# untitled.net
KiCad netlist of a schematic drawn in EAGLE
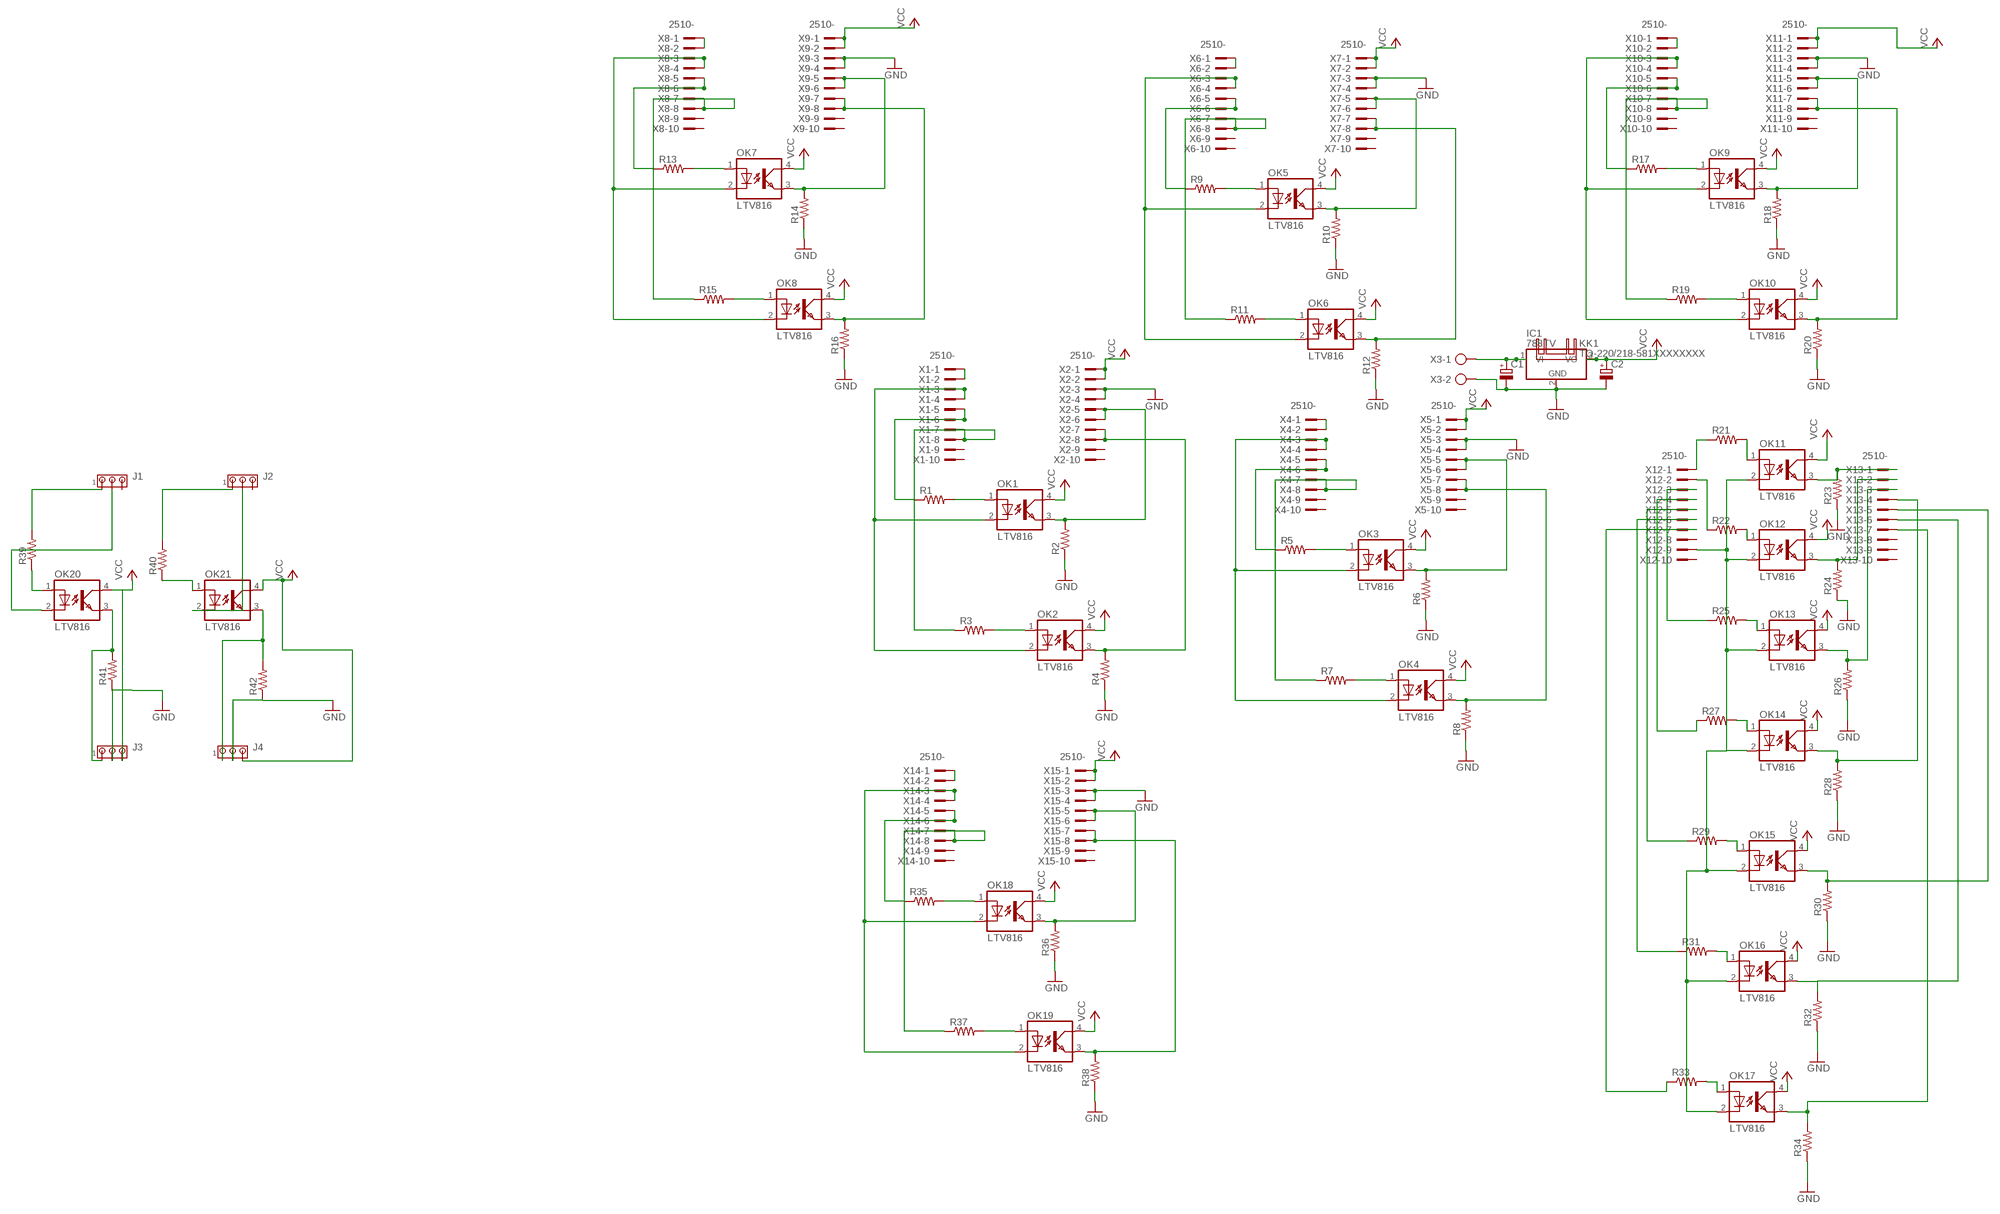
[diagram p0: schematic, sheet 1]

(export (version "E")
  (design (tool "Eeschema 10.0.6"))
  (components
    (comp (ref "C1")
      (value "CPOL-EUE5-13")
      (footprint "eagle-import:E5-13")
      (libsource (lib "eagle-import") (part "CPOL-EUE5-13"))
    )
    (comp (ref "C2")
      (value "CPOL-EUE5-10.5")
      (footprint "eagle-import:E5-10,5")
      (libsource (lib "eagle-import") (part "CPOL-EUE5-10.5"))
    )
    (comp (ref "IC1")
      (value "788TV")
      (footprint "eagle-import:TO220V")
      (libsource (lib "eagle-import") (part "78TV8"))
    )
    (comp (ref "J1")
      (value "MTA03-100")
      (footprint "eagle-import:10X03MTA")
      (libsource (lib "eagle-import") (part "MTA03-100"))
    )
    (comp (ref "J2")
      (value "MTA03-100")
      (footprint "eagle-import:10X03MTA")
      (libsource (lib "eagle-import") (part "MTA03-100"))
    )
    (comp (ref "J3")
      (value "MTA03-100")
      (footprint "eagle-import:10X03MTA")
      (libsource (lib "eagle-import") (part "MTA03-100"))
    )
    (comp (ref "J4")
      (value "MTA03-100")
      (footprint "eagle-import:10X03MTA")
      (libsource (lib "eagle-import") (part "MTA03-100"))
    )
    (comp (ref "KK1")
      (value "TO-220/218-581XXXXXXXX")
      (footprint "eagle-import:581XXXXXXXX")
      (libsource (lib "eagle-import") (part "TO-220/218-581XXXXXXXX"))
    )
    (comp (ref "OK1")
      (value "LTV816")
      (footprint "eagle-import:DIL04")
      (libsource (lib "eagle-import") (part "LTV816"))
    )
    (comp (ref "OK2")
      (value "LTV816")
      (footprint "eagle-import:DIL04")
      (libsource (lib "eagle-import") (part "LTV816"))
    )
    (comp (ref "OK3")
      (value "LTV816")
      (footprint "eagle-import:DIL04")
      (libsource (lib "eagle-import") (part "LTV816"))
    )
    (comp (ref "OK4")
      (value "LTV816")
      (footprint "eagle-import:DIL04")
      (libsource (lib "eagle-import") (part "LTV816"))
    )
    (comp (ref "OK5")
      (value "LTV816")
      (footprint "eagle-import:DIL04")
      (libsource (lib "eagle-import") (part "LTV816"))
    )
    (comp (ref "OK6")
      (value "LTV816")
      (footprint "eagle-import:DIL04")
      (libsource (lib "eagle-import") (part "LTV816"))
    )
    (comp (ref "OK7")
      (value "LTV816")
      (footprint "eagle-import:DIL04")
      (libsource (lib "eagle-import") (part "LTV816"))
    )
    (comp (ref "OK8")
      (value "LTV816")
      (footprint "eagle-import:DIL04")
      (libsource (lib "eagle-import") (part "LTV816"))
    )
    (comp (ref "OK9")
      (value "LTV816")
      (footprint "eagle-import:DIL04")
      (libsource (lib "eagle-import") (part "LTV816"))
    )
    (comp (ref "OK10")
      (value "LTV816")
      (footprint "eagle-import:DIL04")
      (libsource (lib "eagle-import") (part "LTV816"))
    )
    (comp (ref "OK11")
      (value "LTV816")
      (footprint "eagle-import:DIL04")
      (fields (field (name "OC_FARNELL") "unknown") (field (name "OC_NEWARK") "unknown"))
      (libsource (lib "eagle-import") (part "LTV816"))
    )
    (comp (ref "OK12")
      (value "LTV816")
      (footprint "eagle-import:DIL04")
      (fields (field (name "OC_FARNELL") "unknown") (field (name "OC_NEWARK") "unknown"))
      (libsource (lib "eagle-import") (part "LTV816"))
    )
    (comp (ref "OK13")
      (value "LTV816")
      (footprint "eagle-import:DIL04")
      (fields (field (name "OC_FARNELL") "unknown") (field (name "OC_NEWARK") "unknown"))
      (libsource (lib "eagle-import") (part "LTV816"))
    )
    (comp (ref "OK14")
      (value "LTV816")
      (footprint "eagle-import:DIL04")
      (fields (field (name "OC_FARNELL") "unknown") (field (name "OC_NEWARK") "unknown"))
      (libsource (lib "eagle-import") (part "LTV816"))
    )
    (comp (ref "OK15")
      (value "LTV816")
      (footprint "eagle-import:DIL04")
      (fields (field (name "OC_FARNELL") "unknown") (field (name "OC_NEWARK") "unknown"))
      (libsource (lib "eagle-import") (part "LTV816"))
    )
    (comp (ref "OK16")
      (value "LTV816")
      (footprint "eagle-import:DIL04")
      (fields (field (name "OC_FARNELL") "unknown") (field (name "OC_NEWARK") "unknown"))
      (libsource (lib "eagle-import") (part "LTV816"))
    )
    (comp (ref "OK17")
      (value "LTV816")
      (footprint "eagle-import:DIL04")
      (fields (field (name "OC_FARNELL") "unknown") (field (name "OC_NEWARK") "unknown"))
      (libsource (lib "eagle-import") (part "LTV816"))
    )
    (comp (ref "OK18")
      (value "LTV816")
      (footprint "eagle-import:DIL04")
      (libsource (lib "eagle-import") (part "LTV816"))
    )
    (comp (ref "OK19")
      (value "LTV816")
      (footprint "eagle-import:DIL04")
      (libsource (lib "eagle-import") (part "LTV816"))
    )
    (comp (ref "OK20")
      (value "LTV816")
      (footprint "eagle-import:DIL04")
      (fields (field (name "OC_FARNELL") "unknown") (field (name "OC_NEWARK") "unknown"))
      (libsource (lib "eagle-import") (part "LTV816"))
    )
    (comp (ref "OK21")
      (value "LTV816")
      (footprint "eagle-import:DIL04")
      (fields (field (name "OC_FARNELL") "unknown") (field (name "OC_NEWARK") "unknown"))
      (libsource (lib "eagle-import") (part "LTV816"))
    )
    (comp (ref "R1")
      (value "R-US_0207/10")
      (footprint "eagle-import:0207_10")
      (libsource (lib "eagle-import") (part "R-US_0207/10"))
    )
    (comp (ref "R2")
      (value "R-US_0207/10")
      (footprint "eagle-import:0207_10")
      (libsource (lib "eagle-import") (part "R-US_0207/10"))
    )
    (comp (ref "R3")
      (value "R-US_0207/10")
      (footprint "eagle-import:0207_10")
      (libsource (lib "eagle-import") (part "R-US_0207/10"))
    )
    (comp (ref "R4")
      (value "R-US_0207/10")
      (footprint "eagle-import:0207_10")
      (libsource (lib "eagle-import") (part "R-US_0207/10"))
    )
    (comp (ref "R5")
      (value "R-US_0207/10")
      (footprint "eagle-import:0207_10")
      (libsource (lib "eagle-import") (part "R-US_0207/10"))
    )
    (comp (ref "R6")
      (value "R-US_0207/10")
      (footprint "eagle-import:0207_10")
      (libsource (lib "eagle-import") (part "R-US_0207/10"))
    )
    (comp (ref "R7")
      (value "R-US_0207/10")
      (footprint "eagle-import:0207_10")
      (libsource (lib "eagle-import") (part "R-US_0207/10"))
    )
    (comp (ref "R8")
      (value "R-US_0207/10")
      (footprint "eagle-import:0207_10")
      (libsource (lib "eagle-import") (part "R-US_0207/10"))
    )
    (comp (ref "R9")
      (value "R-US_0207/10")
      (footprint "eagle-import:0207_10")
      (libsource (lib "eagle-import") (part "R-US_0207/10"))
    )
    (comp (ref "R10")
      (value "R-US_0207/10")
      (footprint "eagle-import:0207_10")
      (libsource (lib "eagle-import") (part "R-US_0207/10"))
    )
    (comp (ref "R11")
      (value "R-US_0207/10")
      (footprint "eagle-import:0207_10")
      (libsource (lib "eagle-import") (part "R-US_0207/10"))
    )
    (comp (ref "R12")
      (value "R-US_0207/10")
      (footprint "eagle-import:0207_10")
      (libsource (lib "eagle-import") (part "R-US_0207/10"))
    )
    (comp (ref "R13")
      (value "R-US_0207/10")
      (footprint "eagle-import:0207_10")
      (libsource (lib "eagle-import") (part "R-US_0207/10"))
    )
    (comp (ref "R14")
      (value "R-US_0207/10")
      (footprint "eagle-import:0207_10")
      (libsource (lib "eagle-import") (part "R-US_0207/10"))
    )
    (comp (ref "R15")
      (value "R-US_0207/10")
      (footprint "eagle-import:0207_10")
      (libsource (lib "eagle-import") (part "R-US_0207/10"))
    )
    (comp (ref "R16")
      (value "R-US_0207/10")
      (footprint "eagle-import:0207_10")
      (libsource (lib "eagle-import") (part "R-US_0207/10"))
    )
    (comp (ref "R17")
      (value "R-US_0207/10")
      (footprint "eagle-import:0207_10")
      (libsource (lib "eagle-import") (part "R-US_0207/10"))
    )
    (comp (ref "R18")
      (value "R-US_0207/10")
      (footprint "eagle-import:0207_10")
      (libsource (lib "eagle-import") (part "R-US_0207/10"))
    )
    (comp (ref "R19")
      (value "R-US_0207/10")
      (footprint "eagle-import:0207_10")
      (libsource (lib "eagle-import") (part "R-US_0207/10"))
    )
    (comp (ref "R20")
      (value "R-US_0207/10")
      (footprint "eagle-import:0207_10")
      (libsource (lib "eagle-import") (part "R-US_0207/10"))
    )
    (comp (ref "R21")
      (value "R-US_0207/10")
      (footprint "eagle-import:0207_10")
      (libsource (lib "eagle-import") (part "R-US_0207/10"))
    )
    (comp (ref "R22")
      (value "R-US_0207/10")
      (footprint "eagle-import:0207_10")
      (libsource (lib "eagle-import") (part "R-US_0207/10"))
    )
    (comp (ref "R23")
      (value "R-US_0207/10")
      (footprint "eagle-import:0207_10")
      (libsource (lib "eagle-import") (part "R-US_0207/10"))
    )
    (comp (ref "R24")
      (value "R-US_0207/10")
      (footprint "eagle-import:0207_10")
      (libsource (lib "eagle-import") (part "R-US_0207/10"))
    )
    (comp (ref "R25")
      (value "R-US_0207/10")
      (footprint "eagle-import:0207_10")
      (libsource (lib "eagle-import") (part "R-US_0207/10"))
    )
    (comp (ref "R26")
      (value "R-US_0207/10")
      (footprint "eagle-import:0207_10")
      (libsource (lib "eagle-import") (part "R-US_0207/10"))
    )
    (comp (ref "R27")
      (value "R-US_0207/10")
      (footprint "eagle-import:0207_10")
      (libsource (lib "eagle-import") (part "R-US_0207/10"))
    )
    (comp (ref "R28")
      (value "R-US_0207/10")
      (footprint "eagle-import:0207_10")
      (libsource (lib "eagle-import") (part "R-US_0207/10"))
    )
    (comp (ref "R29")
      (value "R-US_0207/10")
      (footprint "eagle-import:0207_10")
      (libsource (lib "eagle-import") (part "R-US_0207/10"))
    )
    (comp (ref "R30")
      (value "R-US_0207/10")
      (footprint "eagle-import:0207_10")
      (libsource (lib "eagle-import") (part "R-US_0207/10"))
    )
    (comp (ref "R31")
      (value "R-US_0207/10")
      (footprint "eagle-import:0207_10")
      (libsource (lib "eagle-import") (part "R-US_0207/10"))
    )
    (comp (ref "R32")
      (value "R-US_0207/10")
      (footprint "eagle-import:0207_10")
      (libsource (lib "eagle-import") (part "R-US_0207/10"))
    )
    (comp (ref "R33")
      (value "R-US_0207/10")
      (footprint "eagle-import:0207_10")
      (libsource (lib "eagle-import") (part "R-US_0207/10"))
    )
    (comp (ref "R34")
      (value "R-US_0207/10")
      (footprint "eagle-import:0207_10")
      (libsource (lib "eagle-import") (part "R-US_0207/10"))
    )
    (comp (ref "R35")
      (value "R-US_0207/10")
      (footprint "eagle-import:0207_10")
      (libsource (lib "eagle-import") (part "R-US_0207/10"))
    )
    (comp (ref "R36")
      (value "R-US_0207/10")
      (footprint "eagle-import:0207_10")
      (libsource (lib "eagle-import") (part "R-US_0207/10"))
    )
    (comp (ref "R37")
      (value "R-US_0207/10")
      (footprint "eagle-import:0207_10")
      (libsource (lib "eagle-import") (part "R-US_0207/10"))
    )
    (comp (ref "R38")
      (value "R-US_0207/10")
      (footprint "eagle-import:0207_10")
      (libsource (lib "eagle-import") (part "R-US_0207/10"))
    )
    (comp (ref "R39")
      (value "R-US_0207/10")
      (footprint "eagle-import:0207_10")
      (libsource (lib "eagle-import") (part "R-US_0207/10"))
    )
    (comp (ref "R40")
      (value "R-US_0207/10")
      (footprint "eagle-import:0207_10")
      (libsource (lib "eagle-import") (part "R-US_0207/10"))
    )
    (comp (ref "R41")
      (value "R-US_0207/10")
      (footprint "eagle-import:0207_10")
      (libsource (lib "eagle-import") (part "R-US_0207/10"))
    )
    (comp (ref "R42")
      (value "R-US_0207/10")
      (footprint "eagle-import:0207_10")
      (libsource (lib "eagle-import") (part "R-US_0207/10"))
    )
    (comp (ref "X1")
      (value "2510-")
      (footprint "eagle-import:PAK100_2500-10")
      (fields (field (name "MF") "3M") (field (name "MPN") "2510-6002UB"))
      (libsource (lib "eagle-import") (part "2510-"))
    )
    (comp (ref "X2")
      (value "2510-")
      (footprint "eagle-import:PAK100_2500-10")
      (fields (field (name "MF") "3M") (field (name "MPN") "2510-6002UB"))
      (libsource (lib "eagle-import") (part "2510-"))
    )
    (comp (ref "X3")
      (value "AK300/2")
      (footprint "eagle-import:AK300_2")
      (libsource (lib "eagle-import") (part "AK300/2"))
    )
    (comp (ref "X4")
      (value "2510-")
      (footprint "eagle-import:PAK100_2500-10")
      (fields (field (name "MF") "3M") (field (name "MPN") "2510-6002UB"))
      (libsource (lib "eagle-import") (part "2510-"))
    )
    (comp (ref "X5")
      (value "2510-")
      (footprint "eagle-import:PAK100_2500-10")
      (fields (field (name "MF") "3M") (field (name "MPN") "2510-6002UB"))
      (libsource (lib "eagle-import") (part "2510-"))
    )
    (comp (ref "X6")
      (value "2510-")
      (footprint "eagle-import:PAK100_2500-10")
      (fields (field (name "MF") "3M") (field (name "MPN") "2510-6002UB"))
      (libsource (lib "eagle-import") (part "2510-"))
    )
    (comp (ref "X7")
      (value "2510-")
      (footprint "eagle-import:PAK100_2500-10")
      (fields (field (name "MF") "3M") (field (name "MPN") "2510-6002UB"))
      (libsource (lib "eagle-import") (part "2510-"))
    )
    (comp (ref "X8")
      (value "2510-")
      (footprint "eagle-import:PAK100_2500-10")
      (fields (field (name "MF") "3M") (field (name "MPN") "2510-6002UB"))
      (libsource (lib "eagle-import") (part "2510-"))
    )
    (comp (ref "X9")
      (value "2510-")
      (footprint "eagle-import:PAK100_2500-10")
      (fields (field (name "MF") "3M") (field (name "MPN") "2510-6002UB"))
      (libsource (lib "eagle-import") (part "2510-"))
    )
    (comp (ref "X10")
      (value "2510-")
      (footprint "eagle-import:PAK100_2500-10")
      (fields (field (name "MF") "3M") (field (name "MPN") "2510-6002UB"))
      (libsource (lib "eagle-import") (part "2510-"))
    )
    (comp (ref "X11")
      (value "2510-")
      (footprint "eagle-import:PAK100_2500-10")
      (fields (field (name "MF") "3M") (field (name "MPN") "2510-6002UB"))
      (libsource (lib "eagle-import") (part "2510-"))
    )
    (comp (ref "X12")
      (value "2510-")
      (footprint "eagle-import:PAK100_2500-10")
      (fields (field (name "MF") "3M") (field (name "MPN") "2510-6002UB"))
      (libsource (lib "eagle-import") (part "2510-"))
    )
    (comp (ref "X13")
      (value "2510-")
      (footprint "eagle-import:PAK100_2500-10")
      (fields (field (name "MF") "3M") (field (name "MPN") "2510-6002UB"))
      (libsource (lib "eagle-import") (part "2510-"))
    )
    (comp (ref "X14")
      (value "2510-")
      (footprint "eagle-import:PAK100_2500-10")
      (fields (field (name "MF") "3M") (field (name "MPN") "2510-6002UB"))
      (libsource (lib "eagle-import") (part "2510-"))
    )
    (comp (ref "X15")
      (value "2510-")
      (footprint "eagle-import:PAK100_2500-10")
      (fields (field (name "MF") "3M") (field (name "MPN") "2510-6002UB"))
      (libsource (lib "eagle-import") (part "2510-"))
    )
  )
  (nets
    (net (code "1") (name "GND") (class "Default")
      (node (ref "C1") (pin "-") (pinfunction "-_-") (pintype "passive"))
      (node (ref "C2") (pin "-") (pinfunction "-_-") (pintype "passive"))
      (node (ref "IC1") (pin "2") (pinfunction "GND_2") (pintype "passive"))
      (node (ref "J3") (pin "2") (pinfunction "2_2") (pintype "passive"))
      (node (ref "J4") (pin "2") (pinfunction "2_2") (pintype "passive"))
      (node (ref "R10") (pin "1") (pinfunction "1_1") (pintype "passive"))
      (node (ref "R12") (pin "1") (pinfunction "1_1") (pintype "passive"))
      (node (ref "R14") (pin "1") (pinfunction "1_1") (pintype "passive"))
      (node (ref "R16") (pin "1") (pinfunction "1_1") (pintype "passive"))
      (node (ref "R18") (pin "1") (pinfunction "1_1") (pintype "passive"))
      (node (ref "R2") (pin "1") (pinfunction "1_1") (pintype "passive"))
      (node (ref "R20") (pin "1") (pinfunction "1_1") (pintype "passive"))
      (node (ref "R23") (pin "1") (pinfunction "1_1") (pintype "passive"))
      (node (ref "R24") (pin "1") (pinfunction "1_1") (pintype "passive"))
      (node (ref "R26") (pin "1") (pinfunction "1_1") (pintype "passive"))
      (node (ref "R28") (pin "1") (pinfunction "1_1") (pintype "passive"))
      (node (ref "R30") (pin "1") (pinfunction "1_1") (pintype "passive"))
      (node (ref "R32") (pin "1") (pinfunction "1_1") (pintype "passive"))
      (node (ref "R34") (pin "1") (pinfunction "1_1") (pintype "passive"))
      (node (ref "R36") (pin "1") (pinfunction "1_1") (pintype "passive"))
      (node (ref "R38") (pin "1") (pinfunction "1_1") (pintype "passive"))
      (node (ref "R4") (pin "1") (pinfunction "1_1") (pintype "passive"))
      (node (ref "R41") (pin "1") (pinfunction "1_1") (pintype "passive"))
      (node (ref "R42") (pin "1") (pinfunction "1_1") (pintype "passive"))
      (node (ref "R6") (pin "1") (pinfunction "1_1") (pintype "passive"))
      (node (ref "R8") (pin "1") (pinfunction "1_1") (pintype "passive"))
      (node (ref "X11") (pin "3") (pinfunction "KL_3") (pintype "passive"))
      (node (ref "X11") (pin "4") (pinfunction "KL_4") (pintype "passive"))
      (node (ref "X15") (pin "3") (pinfunction "KL_3") (pintype "passive"))
      (node (ref "X15") (pin "4") (pinfunction "KL_4") (pintype "passive"))
      (node (ref "X2") (pin "3") (pinfunction "KL_3") (pintype "passive"))
      (node (ref "X2") (pin "4") (pinfunction "KL_4") (pintype "passive"))
      (node (ref "X3") (pin "2") (pinfunction "KL_2") (pintype "passive"))
      (node (ref "X5") (pin "3") (pinfunction "KL_3") (pintype "passive"))
      (node (ref "X5") (pin "4") (pinfunction "KL_4") (pintype "passive"))
      (node (ref "X7") (pin "3") (pinfunction "KL_3") (pintype "passive"))
      (node (ref "X7") (pin "4") (pinfunction "KL_4") (pintype "passive"))
      (node (ref "X9") (pin "3") (pinfunction "KL_3") (pintype "passive"))
      (node (ref "X9") (pin "4") (pinfunction "KL_4") (pintype "passive"))
    )
    (net (code "2") (name "Net-(IC1-VI)") (class "Default")
      (node (ref "C1") (pin "+") (pinfunction "+_+") (pintype "passive"))
      (node (ref "IC1") (pin "1") (pinfunction "VI_1") (pintype "input"))
      (node (ref "X3") (pin "1") (pinfunction "KL_1") (pintype "passive"))
    )
    (net (code "3") (name "Net-(J1-Pad1)") (class "Default")
      (node (ref "J1") (pin "1") (pinfunction "1_1") (pintype "passive"))
      (node (ref "R39") (pin "2") (pinfunction "2_2") (pintype "passive"))
    )
    (net (code "4") (name "Net-(J2-Pad1)") (class "Default")
      (node (ref "J2") (pin "1") (pinfunction "1_1") (pintype "passive"))
      (node (ref "R40") (pin "2") (pinfunction "2_2") (pintype "passive"))
    )
    (net (code "5") (name "Net-(OK1-A)") (class "Default")
      (node (ref "OK1") (pin "1") (pinfunction "A_1") (pintype "passive"))
      (node (ref "R1") (pin "2") (pinfunction "2_2") (pintype "passive"))
    )
    (net (code "6") (name "Net-(OK1-C)") (class "Default")
      (node (ref "OK1") (pin "2") (pinfunction "C_2") (pintype "passive"))
      (node (ref "OK2") (pin "2") (pinfunction "C_2") (pintype "passive"))
      (node (ref "X1") (pin "3") (pinfunction "KL_3") (pintype "passive"))
      (node (ref "X1") (pin "4") (pinfunction "KL_4") (pintype "passive"))
    )
    (net (code "7") (name "Net-(OK1-EMIT)") (class "Default")
      (node (ref "OK1") (pin "3") (pinfunction "EMIT_3") (pintype "passive"))
      (node (ref "R2") (pin "2") (pinfunction "2_2") (pintype "passive"))
      (node (ref "X2") (pin "5") (pinfunction "KL_5") (pintype "passive"))
      (node (ref "X2") (pin "6") (pinfunction "KL_6") (pintype "passive"))
    )
    (net (code "8") (name "Net-(OK2-A)") (class "Default")
      (node (ref "OK2") (pin "1") (pinfunction "A_1") (pintype "passive"))
      (node (ref "R3") (pin "2") (pinfunction "2_2") (pintype "passive"))
    )
    (net (code "9") (name "Net-(OK2-EMIT)") (class "Default")
      (node (ref "OK2") (pin "3") (pinfunction "EMIT_3") (pintype "passive"))
      (node (ref "R4") (pin "2") (pinfunction "2_2") (pintype "passive"))
      (node (ref "X2") (pin "7") (pinfunction "KL_7") (pintype "passive"))
      (node (ref "X2") (pin "8") (pinfunction "KL_8") (pintype "passive"))
    )
    (net (code "10") (name "Net-(OK3-A)") (class "Default")
      (node (ref "OK3") (pin "1") (pinfunction "A_1") (pintype "passive"))
      (node (ref "R5") (pin "2") (pinfunction "2_2") (pintype "passive"))
    )
    (net (code "11") (name "Net-(OK3-C)") (class "Default")
      (node (ref "OK3") (pin "2") (pinfunction "C_2") (pintype "passive"))
      (node (ref "OK4") (pin "2") (pinfunction "C_2") (pintype "passive"))
      (node (ref "X4") (pin "3") (pinfunction "KL_3") (pintype "passive"))
      (node (ref "X4") (pin "4") (pinfunction "KL_4") (pintype "passive"))
    )
    (net (code "12") (name "Net-(OK3-EMIT)") (class "Default")
      (node (ref "OK3") (pin "3") (pinfunction "EMIT_3") (pintype "passive"))
      (node (ref "R6") (pin "2") (pinfunction "2_2") (pintype "passive"))
      (node (ref "X5") (pin "5") (pinfunction "KL_5") (pintype "passive"))
      (node (ref "X5") (pin "6") (pinfunction "KL_6") (pintype "passive"))
    )
    (net (code "13") (name "Net-(OK4-A)") (class "Default")
      (node (ref "OK4") (pin "1") (pinfunction "A_1") (pintype "passive"))
      (node (ref "R7") (pin "2") (pinfunction "2_2") (pintype "passive"))
    )
    (net (code "14") (name "Net-(OK4-EMIT)") (class "Default")
      (node (ref "OK4") (pin "3") (pinfunction "EMIT_3") (pintype "passive"))
      (node (ref "R8") (pin "2") (pinfunction "2_2") (pintype "passive"))
      (node (ref "X5") (pin "7") (pinfunction "KL_7") (pintype "passive"))
      (node (ref "X5") (pin "8") (pinfunction "KL_8") (pintype "passive"))
    )
    (net (code "15") (name "Net-(OK5-A)") (class "Default")
      (node (ref "OK5") (pin "1") (pinfunction "A_1") (pintype "passive"))
      (node (ref "R9") (pin "2") (pinfunction "2_2") (pintype "passive"))
    )
    (net (code "16") (name "Net-(OK5-C)") (class "Default")
      (node (ref "OK5") (pin "2") (pinfunction "C_2") (pintype "passive"))
      (node (ref "OK6") (pin "2") (pinfunction "C_2") (pintype "passive"))
      (node (ref "X6") (pin "3") (pinfunction "KL_3") (pintype "passive"))
      (node (ref "X6") (pin "4") (pinfunction "KL_4") (pintype "passive"))
    )
    (net (code "17") (name "Net-(OK5-EMIT)") (class "Default")
      (node (ref "OK5") (pin "3") (pinfunction "EMIT_3") (pintype "passive"))
      (node (ref "R10") (pin "2") (pinfunction "2_2") (pintype "passive"))
      (node (ref "X7") (pin "5") (pinfunction "KL_5") (pintype "passive"))
      (node (ref "X7") (pin "6") (pinfunction "KL_6") (pintype "passive"))
    )
    (net (code "18") (name "Net-(OK6-A)") (class "Default")
      (node (ref "OK6") (pin "1") (pinfunction "A_1") (pintype "passive"))
      (node (ref "R11") (pin "2") (pinfunction "2_2") (pintype "passive"))
    )
    (net (code "19") (name "Net-(OK6-EMIT)") (class "Default")
      (node (ref "OK6") (pin "3") (pinfunction "EMIT_3") (pintype "passive"))
      (node (ref "R12") (pin "2") (pinfunction "2_2") (pintype "passive"))
      (node (ref "X7") (pin "7") (pinfunction "KL_7") (pintype "passive"))
      (node (ref "X7") (pin "8") (pinfunction "KL_8") (pintype "passive"))
    )
    (net (code "20") (name "Net-(OK7-A)") (class "Default")
      (node (ref "OK7") (pin "1") (pinfunction "A_1") (pintype "passive"))
      (node (ref "R13") (pin "2") (pinfunction "2_2") (pintype "passive"))
    )
    (net (code "21") (name "Net-(OK7-C)") (class "Default")
      (node (ref "OK7") (pin "2") (pinfunction "C_2") (pintype "passive"))
      (node (ref "OK8") (pin "2") (pinfunction "C_2") (pintype "passive"))
      (node (ref "X8") (pin "3") (pinfunction "KL_3") (pintype "passive"))
      (node (ref "X8") (pin "4") (pinfunction "KL_4") (pintype "passive"))
    )
    (net (code "22") (name "Net-(OK7-EMIT)") (class "Default")
      (node (ref "OK7") (pin "3") (pinfunction "EMIT_3") (pintype "passive"))
      (node (ref "R14") (pin "2") (pinfunction "2_2") (pintype "passive"))
      (node (ref "X9") (pin "5") (pinfunction "KL_5") (pintype "passive"))
      (node (ref "X9") (pin "6") (pinfunction "KL_6") (pintype "passive"))
    )
    (net (code "23") (name "Net-(OK8-A)") (class "Default")
      (node (ref "OK8") (pin "1") (pinfunction "A_1") (pintype "passive"))
      (node (ref "R15") (pin "2") (pinfunction "2_2") (pintype "passive"))
    )
    (net (code "24") (name "Net-(OK8-EMIT)") (class "Default")
      (node (ref "OK8") (pin "3") (pinfunction "EMIT_3") (pintype "passive"))
      (node (ref "R16") (pin "2") (pinfunction "2_2") (pintype "passive"))
      (node (ref "X9") (pin "7") (pinfunction "KL_7") (pintype "passive"))
      (node (ref "X9") (pin "8") (pinfunction "KL_8") (pintype "passive"))
    )
    (net (code "25") (name "Net-(OK9-A)") (class "Default")
      (node (ref "OK9") (pin "1") (pinfunction "A_1") (pintype "passive"))
      (node (ref "R17") (pin "2") (pinfunction "2_2") (pintype "passive"))
    )
    (net (code "26") (name "Net-(OK9-EMIT)") (class "Default")
      (node (ref "OK9") (pin "3") (pinfunction "EMIT_3") (pintype "passive"))
      (node (ref "R18") (pin "2") (pinfunction "2_2") (pintype "passive"))
      (node (ref "X11") (pin "5") (pinfunction "KL_5") (pintype "passive"))
      (node (ref "X11") (pin "6") (pinfunction "KL_6") (pintype "passive"))
    )
    (net (code "27") (name "Net-(OK10-A)") (class "Default")
      (node (ref "OK10") (pin "1") (pinfunction "A_1") (pintype "passive"))
      (node (ref "R19") (pin "2") (pinfunction "2_2") (pintype "passive"))
    )
    (net (code "28") (name "Net-(OK10-C)") (class "Default")
      (node (ref "OK10") (pin "2") (pinfunction "C_2") (pintype "passive"))
      (node (ref "OK9") (pin "2") (pinfunction "C_2") (pintype "passive"))
      (node (ref "X10") (pin "3") (pinfunction "KL_3") (pintype "passive"))
      (node (ref "X10") (pin "4") (pinfunction "KL_4") (pintype "passive"))
    )
    (net (code "29") (name "Net-(OK10-EMIT)") (class "Default")
      (node (ref "OK10") (pin "3") (pinfunction "EMIT_3") (pintype "passive"))
      (node (ref "R20") (pin "2") (pinfunction "2_2") (pintype "passive"))
      (node (ref "X11") (pin "7") (pinfunction "KL_7") (pintype "passive"))
      (node (ref "X11") (pin "8") (pinfunction "KL_8") (pintype "passive"))
    )
    (net (code "30") (name "Net-(OK11-A)") (class "Default")
      (node (ref "OK11") (pin "1") (pinfunction "A_1") (pintype "passive"))
      (node (ref "R21") (pin "2") (pinfunction "2_2") (pintype "passive"))
    )
    (net (code "31") (name "Net-(OK11-C)") (class "Default")
      (node (ref "OK11") (pin "2") (pinfunction "C_2") (pintype "passive"))
      (node (ref "OK12") (pin "2") (pinfunction "C_2") (pintype "passive"))
      (node (ref "OK13") (pin "2") (pinfunction "C_2") (pintype "passive"))
      (node (ref "OK14") (pin "2") (pinfunction "C_2") (pintype "passive"))
      (node (ref "OK15") (pin "2") (pinfunction "C_2") (pintype "passive"))
      (node (ref "OK16") (pin "2") (pinfunction "C_2") (pintype "passive"))
      (node (ref "OK17") (pin "2") (pinfunction "C_2") (pintype "passive"))
      (node (ref "X12") (pin "9") (pinfunction "KL_9") (pintype "passive"))
    )
    (net (code "32") (name "Net-(OK11-EMIT)") (class "Default")
      (node (ref "OK11") (pin "3") (pinfunction "EMIT_3") (pintype "passive"))
      (node (ref "R23") (pin "2") (pinfunction "2_2") (pintype "passive"))
      (node (ref "X13") (pin "1") (pinfunction "KL_1") (pintype "passive"))
    )
    (net (code "33") (name "Net-(OK12-A)") (class "Default")
      (node (ref "OK12") (pin "1") (pinfunction "A_1") (pintype "passive"))
      (node (ref "R22") (pin "2") (pinfunction "2_2") (pintype "passive"))
    )
    (net (code "34") (name "Net-(OK12-EMIT)") (class "Default")
      (node (ref "OK12") (pin "3") (pinfunction "EMIT_3") (pintype "passive"))
      (node (ref "R24") (pin "2") (pinfunction "2_2") (pintype "passive"))
      (node (ref "X13") (pin "2") (pinfunction "KL_2") (pintype "passive"))
    )
    (net (code "35") (name "Net-(OK13-A)") (class "Default")
      (node (ref "OK13") (pin "1") (pinfunction "A_1") (pintype "passive"))
      (node (ref "R25") (pin "2") (pinfunction "2_2") (pintype "passive"))
    )
    (net (code "36") (name "Net-(OK13-EMIT)") (class "Default")
      (node (ref "OK13") (pin "3") (pinfunction "EMIT_3") (pintype "passive"))
      (node (ref "R26") (pin "2") (pinfunction "2_2") (pintype "passive"))
      (node (ref "X13") (pin "3") (pinfunction "KL_3") (pintype "passive"))
    )
    (net (code "37") (name "Net-(OK14-A)") (class "Default")
      (node (ref "OK14") (pin "1") (pinfunction "A_1") (pintype "passive"))
      (node (ref "R27") (pin "2") (pinfunction "2_2") (pintype "passive"))
    )
    (net (code "38") (name "Net-(OK14-EMIT)") (class "Default")
      (node (ref "OK14") (pin "3") (pinfunction "EMIT_3") (pintype "passive"))
      (node (ref "R28") (pin "2") (pinfunction "2_2") (pintype "passive"))
      (node (ref "X13") (pin "4") (pinfunction "KL_4") (pintype "passive"))
    )
    (net (code "39") (name "Net-(OK15-A)") (class "Default")
      (node (ref "OK15") (pin "1") (pinfunction "A_1") (pintype "passive"))
      (node (ref "R29") (pin "2") (pinfunction "2_2") (pintype "passive"))
    )
    (net (code "40") (name "Net-(OK15-EMIT)") (class "Default")
      (node (ref "OK15") (pin "3") (pinfunction "EMIT_3") (pintype "passive"))
      (node (ref "R30") (pin "2") (pinfunction "2_2") (pintype "passive"))
      (node (ref "X13") (pin "5") (pinfunction "KL_5") (pintype "passive"))
    )
    (net (code "41") (name "Net-(OK16-A)") (class "Default")
      (node (ref "OK16") (pin "1") (pinfunction "A_1") (pintype "passive"))
      (node (ref "R31") (pin "2") (pinfunction "2_2") (pintype "passive"))
    )
    (net (code "42") (name "Net-(OK16-EMIT)") (class "Default")
      (node (ref "OK16") (pin "3") (pinfunction "EMIT_3") (pintype "passive"))
      (node (ref "R32") (pin "2") (pinfunction "2_2") (pintype "passive"))
      (node (ref "X13") (pin "6") (pinfunction "KL_6") (pintype "passive"))
    )
    (net (code "43") (name "Net-(OK17-A)") (class "Default")
      (node (ref "OK17") (pin "1") (pinfunction "A_1") (pintype "passive"))
      (node (ref "R33") (pin "2") (pinfunction "2_2") (pintype "passive"))
    )
    (net (code "44") (name "Net-(OK17-EMIT)") (class "Default")
      (node (ref "OK17") (pin "3") (pinfunction "EMIT_3") (pintype "passive"))
      (node (ref "R34") (pin "2") (pinfunction "2_2") (pintype "passive"))
      (node (ref "X13") (pin "7") (pinfunction "KL_7") (pintype "passive"))
    )
    (net (code "45") (name "Net-(OK18-A)") (class "Default")
      (node (ref "OK18") (pin "1") (pinfunction "A_1") (pintype "passive"))
      (node (ref "R35") (pin "2") (pinfunction "2_2") (pintype "passive"))
    )
    (net (code "46") (name "Net-(OK18-C)") (class "Default")
      (node (ref "OK18") (pin "2") (pinfunction "C_2") (pintype "passive"))
      (node (ref "OK19") (pin "2") (pinfunction "C_2") (pintype "passive"))
      (node (ref "X14") (pin "3") (pinfunction "KL_3") (pintype "passive"))
      (node (ref "X14") (pin "4") (pinfunction "KL_4") (pintype "passive"))
    )
    (net (code "47") (name "Net-(OK18-EMIT)") (class "Default")
      (node (ref "OK18") (pin "3") (pinfunction "EMIT_3") (pintype "passive"))
      (node (ref "R36") (pin "2") (pinfunction "2_2") (pintype "passive"))
      (node (ref "X15") (pin "5") (pinfunction "KL_5") (pintype "passive"))
      (node (ref "X15") (pin "6") (pinfunction "KL_6") (pintype "passive"))
    )
    (net (code "48") (name "Net-(OK19-A)") (class "Default")
      (node (ref "OK19") (pin "1") (pinfunction "A_1") (pintype "passive"))
      (node (ref "R37") (pin "2") (pinfunction "2_2") (pintype "passive"))
    )
    (net (code "49") (name "Net-(OK19-EMIT)") (class "Default")
      (node (ref "OK19") (pin "3") (pinfunction "EMIT_3") (pintype "passive"))
      (node (ref "R38") (pin "2") (pinfunction "2_2") (pintype "passive"))
      (node (ref "X15") (pin "7") (pinfunction "KL_7") (pintype "passive"))
      (node (ref "X15") (pin "8") (pinfunction "KL_8") (pintype "passive"))
    )
    (net (code "50") (name "Net-(OK20-A)") (class "Default")
      (node (ref "OK20") (pin "1") (pinfunction "A_1") (pintype "passive"))
      (node (ref "R39") (pin "1") (pinfunction "1_1") (pintype "passive"))
    )
    (net (code "51") (name "Net-(OK20-C)") (class "Default")
      (node (ref "J1") (pin "2") (pinfunction "2_2") (pintype "passive"))
      (node (ref "OK20") (pin "2") (pinfunction "C_2") (pintype "passive"))
    )
    (net (code "52") (name "Net-(OK20-EMIT)") (class "Default")
      (node (ref "J3") (pin "1") (pinfunction "1_1") (pintype "passive"))
      (node (ref "OK20") (pin "3") (pinfunction "EMIT_3") (pintype "passive"))
      (node (ref "R41") (pin "2") (pinfunction "2_2") (pintype "passive"))
    )
    (net (code "53") (name "Net-(OK21-A)") (class "Default")
      (node (ref "OK21") (pin "1") (pinfunction "A_1") (pintype "passive"))
      (node (ref "R40") (pin "1") (pinfunction "1_1") (pintype "passive"))
    )
    (net (code "54") (name "Net-(OK21-C)") (class "Default")
      (node (ref "J2") (pin "2") (pinfunction "2_2") (pintype "passive"))
      (node (ref "OK21") (pin "2") (pinfunction "C_2") (pintype "passive"))
    )
    (net (code "55") (name "Net-(OK21-EMIT)") (class "Default")
      (node (ref "J4") (pin "1") (pinfunction "1_1") (pintype "passive"))
      (node (ref "OK21") (pin "3") (pinfunction "EMIT_3") (pintype "passive"))
      (node (ref "R42") (pin "2") (pinfunction "2_2") (pintype "passive"))
    )
    (net (code "56") (name "Net-(X1A-KL)") (class "Default")
      (node (ref "X1") (pin "1") (pinfunction "KL_1") (pintype "passive"))
      (node (ref "X1") (pin "2") (pinfunction "KL_2") (pintype "passive"))
    )
    (net (code "57") (name "Net-(X1F-KL)") (class "Default")
      (node (ref "R1") (pin "1") (pinfunction "1_1") (pintype "passive"))
      (node (ref "X1") (pin "5") (pinfunction "KL_5") (pintype "passive"))
      (node (ref "X1") (pin "6") (pinfunction "KL_6") (pintype "passive"))
    )
    (net (code "58") (name "Net-(X1H-KL)") (class "Default")
      (node (ref "R3") (pin "1") (pinfunction "1_1") (pintype "passive"))
      (node (ref "X1") (pin "7") (pinfunction "KL_7") (pintype "passive"))
      (node (ref "X1") (pin "8") (pinfunction "KL_8") (pintype "passive"))
    )
    (net (code "59") (name "Net-(X4A-KL)") (class "Default")
      (node (ref "X4") (pin "1") (pinfunction "KL_1") (pintype "passive"))
      (node (ref "X4") (pin "2") (pinfunction "KL_2") (pintype "passive"))
    )
    (net (code "60") (name "Net-(X4F-KL)") (class "Default")
      (node (ref "R5") (pin "1") (pinfunction "1_1") (pintype "passive"))
      (node (ref "X4") (pin "5") (pinfunction "KL_5") (pintype "passive"))
      (node (ref "X4") (pin "6") (pinfunction "KL_6") (pintype "passive"))
    )
    (net (code "61") (name "Net-(X4H-KL)") (class "Default")
      (node (ref "R7") (pin "1") (pinfunction "1_1") (pintype "passive"))
      (node (ref "X4") (pin "7") (pinfunction "KL_7") (pintype "passive"))
      (node (ref "X4") (pin "8") (pinfunction "KL_8") (pintype "passive"))
    )
    (net (code "62") (name "Net-(X6A-KL)") (class "Default")
      (node (ref "X6") (pin "1") (pinfunction "KL_1") (pintype "passive"))
      (node (ref "X6") (pin "2") (pinfunction "KL_2") (pintype "passive"))
    )
    (net (code "63") (name "Net-(X6F-KL)") (class "Default")
      (node (ref "R9") (pin "1") (pinfunction "1_1") (pintype "passive"))
      (node (ref "X6") (pin "5") (pinfunction "KL_5") (pintype "passive"))
      (node (ref "X6") (pin "6") (pinfunction "KL_6") (pintype "passive"))
    )
    (net (code "64") (name "Net-(X6H-KL)") (class "Default")
      (node (ref "R11") (pin "1") (pinfunction "1_1") (pintype "passive"))
      (node (ref "X6") (pin "7") (pinfunction "KL_7") (pintype "passive"))
      (node (ref "X6") (pin "8") (pinfunction "KL_8") (pintype "passive"))
    )
    (net (code "65") (name "Net-(X8A-KL)") (class "Default")
      (node (ref "X8") (pin "1") (pinfunction "KL_1") (pintype "passive"))
      (node (ref "X8") (pin "2") (pinfunction "KL_2") (pintype "passive"))
    )
    (net (code "66") (name "Net-(X8F-KL)") (class "Default")
      (node (ref "R13") (pin "1") (pinfunction "1_1") (pintype "passive"))
      (node (ref "X8") (pin "5") (pinfunction "KL_5") (pintype "passive"))
      (node (ref "X8") (pin "6") (pinfunction "KL_6") (pintype "passive"))
    )
    (net (code "67") (name "Net-(X8H-KL)") (class "Default")
      (node (ref "R15") (pin "1") (pinfunction "1_1") (pintype "passive"))
      (node (ref "X8") (pin "7") (pinfunction "KL_7") (pintype "passive"))
      (node (ref "X8") (pin "8") (pinfunction "KL_8") (pintype "passive"))
    )
    (net (code "68") (name "Net-(X10A-KL)") (class "Default")
      (node (ref "X10") (pin "1") (pinfunction "KL_1") (pintype "passive"))
      (node (ref "X10") (pin "2") (pinfunction "KL_2") (pintype "passive"))
    )
    (net (code "69") (name "Net-(X10F-KL)") (class "Default")
      (node (ref "R17") (pin "1") (pinfunction "1_1") (pintype "passive"))
      (node (ref "X10") (pin "5") (pinfunction "KL_5") (pintype "passive"))
      (node (ref "X10") (pin "6") (pinfunction "KL_6") (pintype "passive"))
    )
    (net (code "70") (name "Net-(X10H-KL)") (class "Default")
      (node (ref "R19") (pin "1") (pinfunction "1_1") (pintype "passive"))
      (node (ref "X10") (pin "7") (pinfunction "KL_7") (pintype "passive"))
      (node (ref "X10") (pin "8") (pinfunction "KL_8") (pintype "passive"))
    )
    (net (code "71") (name "Net-(X12A-KL)") (class "Default")
      (node (ref "R21") (pin "1") (pinfunction "1_1") (pintype "passive"))
      (node (ref "X12") (pin "1") (pinfunction "KL_1") (pintype "passive"))
    )
    (net (code "72") (name "Net-(X12C-KL)") (class "Default")
      (node (ref "R22") (pin "1") (pinfunction "1_1") (pintype "passive"))
      (node (ref "X12") (pin "2") (pinfunction "KL_2") (pintype "passive"))
    )
    (net (code "73") (name "Net-(X12D-KL)") (class "Default")
      (node (ref "R25") (pin "1") (pinfunction "1_1") (pintype "passive"))
      (node (ref "X12") (pin "3") (pinfunction "KL_3") (pintype "passive"))
    )
    (net (code "74") (name "Net-(X12E-KL)") (class "Default")
      (node (ref "R27") (pin "1") (pinfunction "1_1") (pintype "passive"))
      (node (ref "X12") (pin "4") (pinfunction "KL_4") (pintype "passive"))
    )
    (net (code "75") (name "Net-(X12F-KL)") (class "Default")
      (node (ref "R29") (pin "1") (pinfunction "1_1") (pintype "passive"))
      (node (ref "X12") (pin "5") (pinfunction "KL_5") (pintype "passive"))
    )
    (net (code "76") (name "Net-(X12G-KL)") (class "Default")
      (node (ref "R31") (pin "1") (pinfunction "1_1") (pintype "passive"))
      (node (ref "X12") (pin "6") (pinfunction "KL_6") (pintype "passive"))
    )
    (net (code "77") (name "Net-(X12H-KL)") (class "Default")
      (node (ref "R33") (pin "1") (pinfunction "1_1") (pintype "passive"))
      (node (ref "X12") (pin "7") (pinfunction "KL_7") (pintype "passive"))
    )
    (net (code "78") (name "Net-(X14A-KL)") (class "Default")
      (node (ref "X14") (pin "1") (pinfunction "KL_1") (pintype "passive"))
      (node (ref "X14") (pin "2") (pinfunction "KL_2") (pintype "passive"))
    )
    (net (code "79") (name "Net-(X14F-KL)") (class "Default")
      (node (ref "R35") (pin "1") (pinfunction "1_1") (pintype "passive"))
      (node (ref "X14") (pin "5") (pinfunction "KL_5") (pintype "passive"))
      (node (ref "X14") (pin "6") (pinfunction "KL_6") (pintype "passive"))
    )
    (net (code "80") (name "Net-(X14H-KL)") (class "Default")
      (node (ref "R37") (pin "1") (pinfunction "1_1") (pintype "passive"))
      (node (ref "X14") (pin "7") (pinfunction "KL_7") (pintype "passive"))
      (node (ref "X14") (pin "8") (pinfunction "KL_8") (pintype "passive"))
    )
    (net (code "81") (name "VCC") (class "Default")
      (node (ref "C2") (pin "+") (pinfunction "+_+") (pintype "passive"))
      (node (ref "IC1") (pin "3") (pinfunction "VO_3") (pintype "passive"))
      (node (ref "J3") (pin "3") (pinfunction "3_3") (pintype "passive"))
      (node (ref "J4") (pin "3") (pinfunction "3_3") (pintype "passive"))
      (node (ref "OK1") (pin "4") (pinfunction "COL_4") (pintype "passive"))
      (node (ref "OK10") (pin "4") (pinfunction "COL_4") (pintype "passive"))
      (node (ref "OK11") (pin "4") (pinfunction "COL_4") (pintype "passive"))
      (node (ref "OK12") (pin "4") (pinfunction "COL_4") (pintype "passive"))
      (node (ref "OK13") (pin "4") (pinfunction "COL_4") (pintype "passive"))
      (node (ref "OK14") (pin "4") (pinfunction "COL_4") (pintype "passive"))
      (node (ref "OK15") (pin "4") (pinfunction "COL_4") (pintype "passive"))
      (node (ref "OK16") (pin "4") (pinfunction "COL_4") (pintype "passive"))
      (node (ref "OK17") (pin "4") (pinfunction "COL_4") (pintype "passive"))
      (node (ref "OK18") (pin "4") (pinfunction "COL_4") (pintype "passive"))
      (node (ref "OK19") (pin "4") (pinfunction "COL_4") (pintype "passive"))
      (node (ref "OK2") (pin "4") (pinfunction "COL_4") (pintype "passive"))
      (node (ref "OK20") (pin "4") (pinfunction "COL_4") (pintype "passive"))
      (node (ref "OK21") (pin "4") (pinfunction "COL_4") (pintype "passive"))
      (node (ref "OK3") (pin "4") (pinfunction "COL_4") (pintype "passive"))
      (node (ref "OK4") (pin "4") (pinfunction "COL_4") (pintype "passive"))
      (node (ref "OK5") (pin "4") (pinfunction "COL_4") (pintype "passive"))
      (node (ref "OK6") (pin "4") (pinfunction "COL_4") (pintype "passive"))
      (node (ref "OK7") (pin "4") (pinfunction "COL_4") (pintype "passive"))
      (node (ref "OK8") (pin "4") (pinfunction "COL_4") (pintype "passive"))
      (node (ref "OK9") (pin "4") (pinfunction "COL_4") (pintype "passive"))
      (node (ref "X11") (pin "1") (pinfunction "KL_1") (pintype "passive"))
      (node (ref "X11") (pin "2") (pinfunction "KL_2") (pintype "passive"))
      (node (ref "X15") (pin "1") (pinfunction "KL_1") (pintype "passive"))
      (node (ref "X15") (pin "2") (pinfunction "KL_2") (pintype "passive"))
      (node (ref "X2") (pin "1") (pinfunction "KL_1") (pintype "passive"))
      (node (ref "X2") (pin "2") (pinfunction "KL_2") (pintype "passive"))
      (node (ref "X5") (pin "1") (pinfunction "KL_1") (pintype "passive"))
      (node (ref "X5") (pin "2") (pinfunction "KL_2") (pintype "passive"))
      (node (ref "X7") (pin "1") (pinfunction "KL_1") (pintype "passive"))
      (node (ref "X7") (pin "2") (pinfunction "KL_2") (pintype "passive"))
      (node (ref "X9") (pin "1") (pinfunction "KL_1") (pintype "passive"))
      (node (ref "X9") (pin "2") (pinfunction "KL_2") (pintype "passive"))
    )
    (net (code "82") (name "unconnected-(J1-Pad3)") (class "Default")
      (node (ref "J1") (pin "3") (pinfunction "3_3") (pintype "passive"))
    )
    (net (code "83") (name "unconnected-(J2-Pad3)") (class "Default")
      (node (ref "J2") (pin "3") (pinfunction "3_3") (pintype "passive"))
    )
    (net (code "84") (name "unconnected-(X1B-KL-Pad10)") (class "Default")
      (node (ref "X1") (pin "10") (pinfunction "KL_10") (pintype "passive"))
    )
    (net (code "85") (name "unconnected-(X1J-KL-Pad9)") (class "Default")
      (node (ref "X1") (pin "9") (pinfunction "KL_9") (pintype "passive"))
    )
    (net (code "86") (name "unconnected-(X2B-KL-Pad10)") (class "Default")
      (node (ref "X2") (pin "10") (pinfunction "KL_10") (pintype "passive"))
    )
    (net (code "87") (name "unconnected-(X2J-KL-Pad9)") (class "Default")
      (node (ref "X2") (pin "9") (pinfunction "KL_9") (pintype "passive"))
    )
    (net (code "88") (name "unconnected-(X4B-KL-Pad10)") (class "Default")
      (node (ref "X4") (pin "10") (pinfunction "KL_10") (pintype "passive"))
    )
    (net (code "89") (name "unconnected-(X4J-KL-Pad9)") (class "Default")
      (node (ref "X4") (pin "9") (pinfunction "KL_9") (pintype "passive"))
    )
    (net (code "90") (name "unconnected-(X5B-KL-Pad10)") (class "Default")
      (node (ref "X5") (pin "10") (pinfunction "KL_10") (pintype "passive"))
    )
    (net (code "91") (name "unconnected-(X5J-KL-Pad9)") (class "Default")
      (node (ref "X5") (pin "9") (pinfunction "KL_9") (pintype "passive"))
    )
    (net (code "92") (name "unconnected-(X6B-KL-Pad10)") (class "Default")
      (node (ref "X6") (pin "10") (pinfunction "KL_10") (pintype "passive"))
    )
    (net (code "93") (name "unconnected-(X6J-KL-Pad9)") (class "Default")
      (node (ref "X6") (pin "9") (pinfunction "KL_9") (pintype "passive"))
    )
    (net (code "94") (name "unconnected-(X7B-KL-Pad10)") (class "Default")
      (node (ref "X7") (pin "10") (pinfunction "KL_10") (pintype "passive"))
    )
    (net (code "95") (name "unconnected-(X7J-KL-Pad9)") (class "Default")
      (node (ref "X7") (pin "9") (pinfunction "KL_9") (pintype "passive"))
    )
    (net (code "96") (name "unconnected-(X8B-KL-Pad10)") (class "Default")
      (node (ref "X8") (pin "10") (pinfunction "KL_10") (pintype "passive"))
    )
    (net (code "97") (name "unconnected-(X8J-KL-Pad9)") (class "Default")
      (node (ref "X8") (pin "9") (pinfunction "KL_9") (pintype "passive"))
    )
    (net (code "98") (name "unconnected-(X9B-KL-Pad10)") (class "Default")
      (node (ref "X9") (pin "10") (pinfunction "KL_10") (pintype "passive"))
    )
    (net (code "99") (name "unconnected-(X9J-KL-Pad9)") (class "Default")
      (node (ref "X9") (pin "9") (pinfunction "KL_9") (pintype "passive"))
    )
    (net (code "100") (name "unconnected-(X10B-KL-Pad10)") (class "Default")
      (node (ref "X10") (pin "10") (pinfunction "KL_10") (pintype "passive"))
    )
    (net (code "101") (name "unconnected-(X10J-KL-Pad9)") (class "Default")
      (node (ref "X10") (pin "9") (pinfunction "KL_9") (pintype "passive"))
    )
    (net (code "102") (name "unconnected-(X11B-KL-Pad10)") (class "Default")
      (node (ref "X11") (pin "10") (pinfunction "KL_10") (pintype "passive"))
    )
    (net (code "103") (name "unconnected-(X11J-KL-Pad9)") (class "Default")
      (node (ref "X11") (pin "9") (pinfunction "KL_9") (pintype "passive"))
    )
    (net (code "104") (name "unconnected-(X12B-KL-Pad10)") (class "Default")
      (node (ref "X12") (pin "10") (pinfunction "KL_10") (pintype "passive"))
    )
    (net (code "105") (name "unconnected-(X12I-KL-Pad8)") (class "Default")
      (node (ref "X12") (pin "8") (pinfunction "KL_8") (pintype "passive"))
    )
    (net (code "106") (name "unconnected-(X13B-KL-Pad10)") (class "Default")
      (node (ref "X13") (pin "10") (pinfunction "KL_10") (pintype "passive"))
    )
    (net (code "107") (name "unconnected-(X13I-KL-Pad8)") (class "Default")
      (node (ref "X13") (pin "8") (pinfunction "KL_8") (pintype "passive"))
    )
    (net (code "108") (name "unconnected-(X13J-KL-Pad9)") (class "Default")
      (node (ref "X13") (pin "9") (pinfunction "KL_9") (pintype "passive"))
    )
    (net (code "109") (name "unconnected-(X14B-KL-Pad10)") (class "Default")
      (node (ref "X14") (pin "10") (pinfunction "KL_10") (pintype "passive"))
    )
    (net (code "110") (name "unconnected-(X14J-KL-Pad9)") (class "Default")
      (node (ref "X14") (pin "9") (pinfunction "KL_9") (pintype "passive"))
    )
    (net (code "111") (name "unconnected-(X15B-KL-Pad10)") (class "Default")
      (node (ref "X15") (pin "10") (pinfunction "KL_10") (pintype "passive"))
    )
    (net (code "112") (name "unconnected-(X15J-KL-Pad9)") (class "Default")
      (node (ref "X15") (pin "9") (pinfunction "KL_9") (pintype "passive"))
    )
  )
)
